# SHEET2.net
KiCad netlist of a schematic drawn in Altium Designer
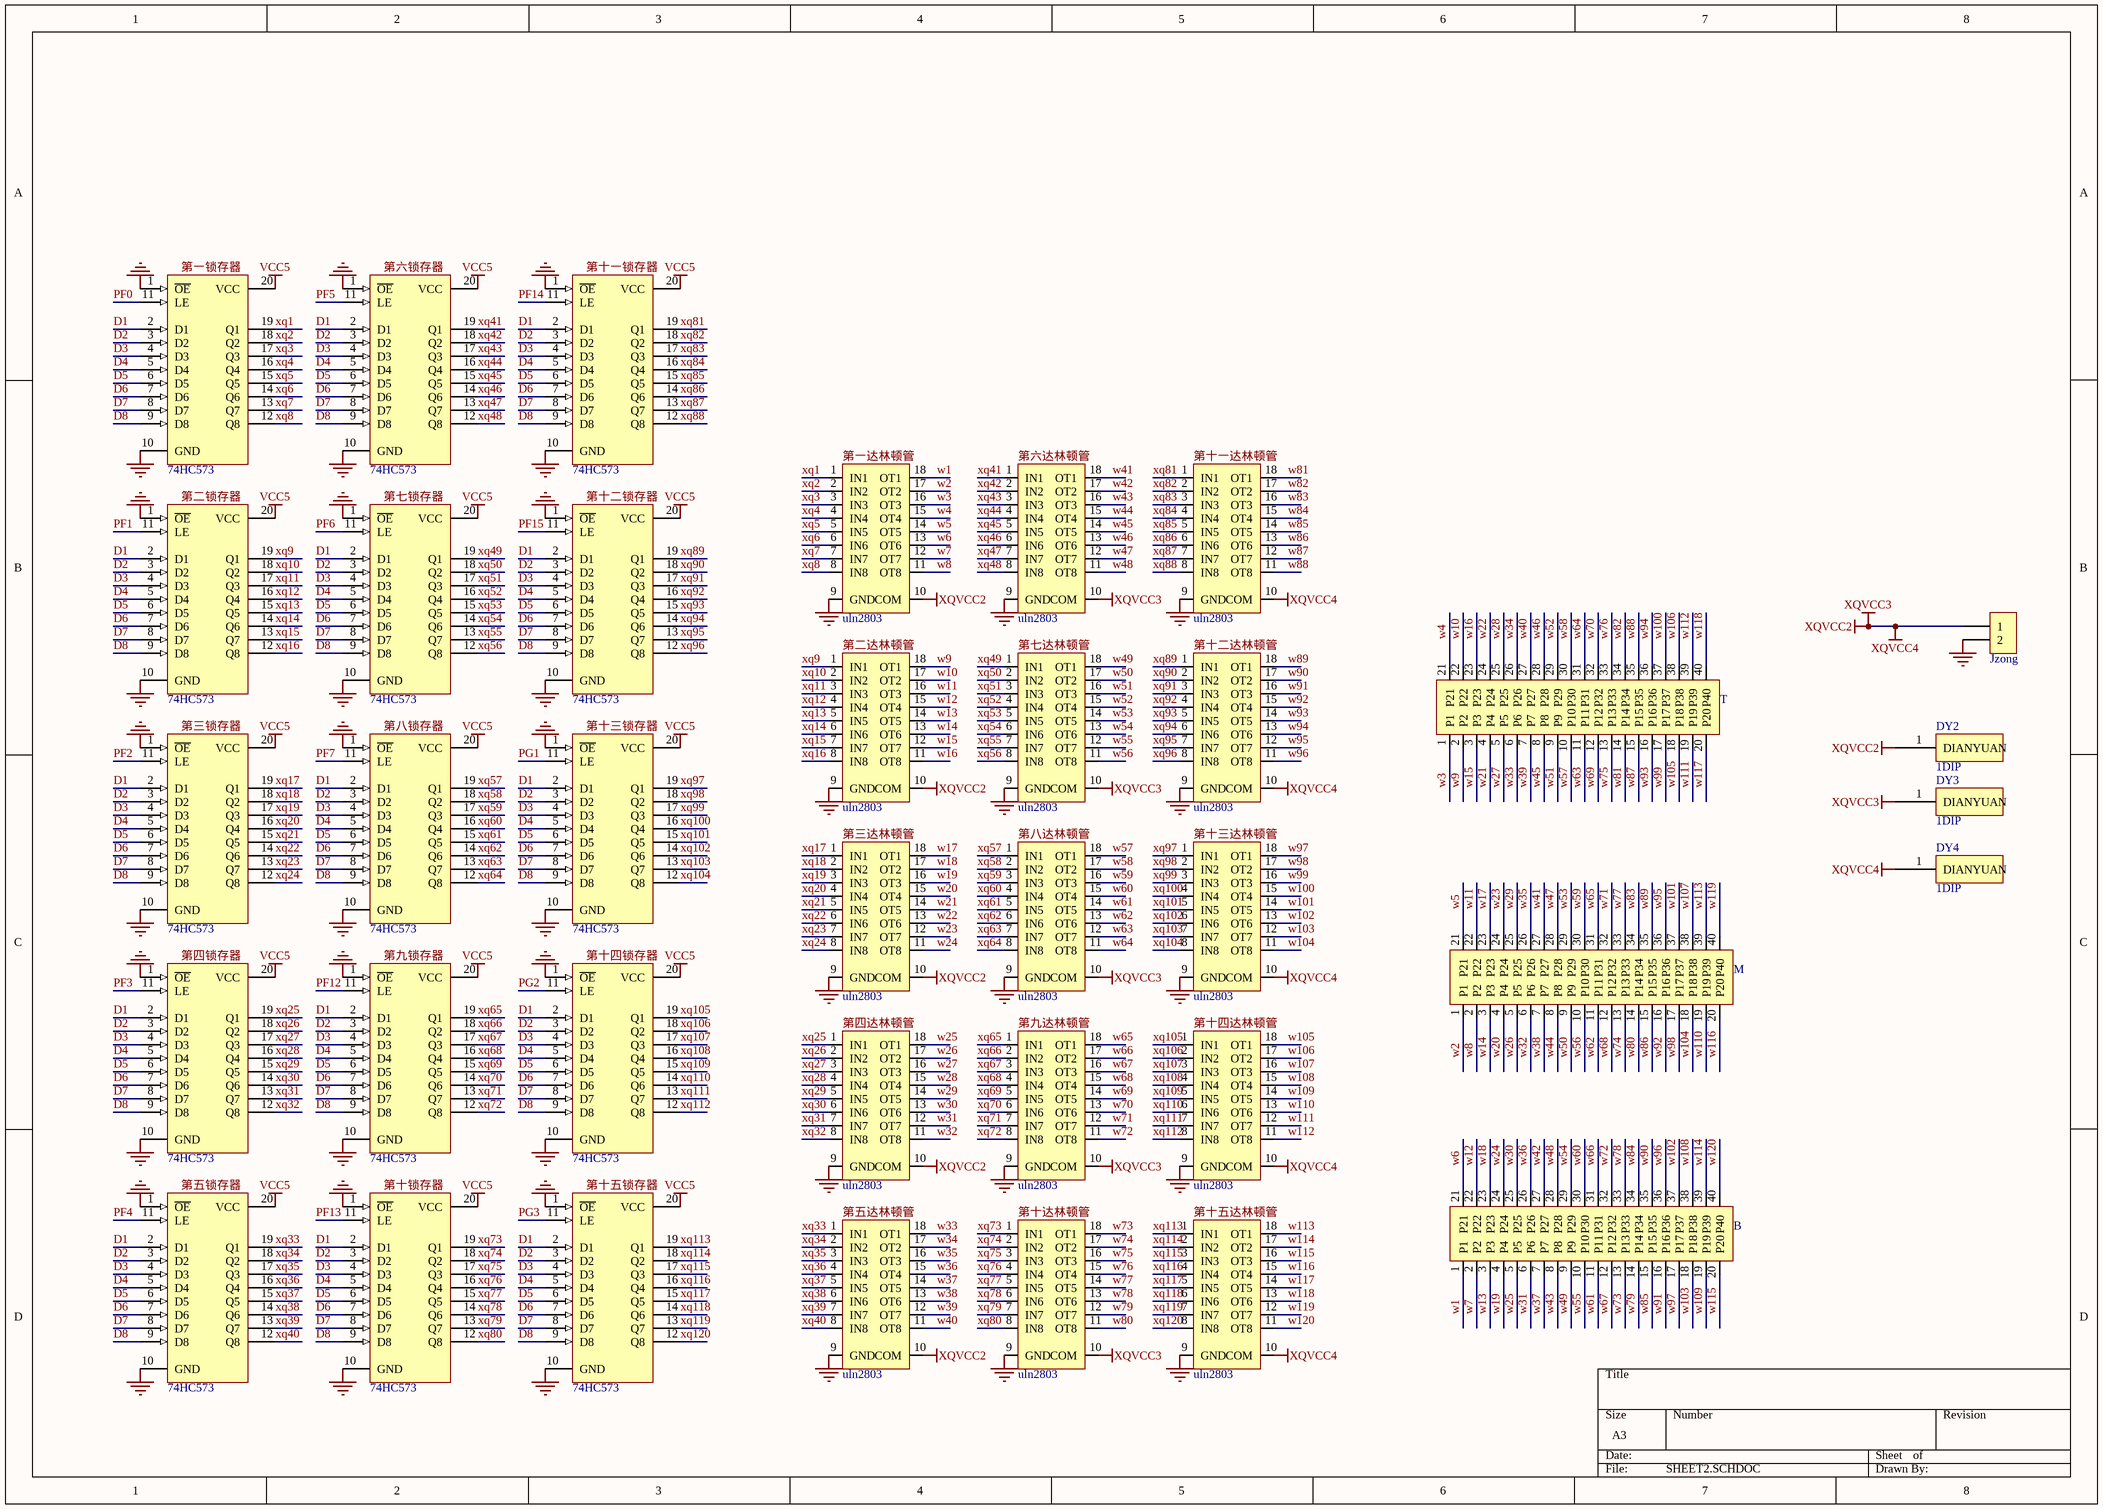
[diagram p0: SHEET2.SCHDOC]

(export (version "E")
  (design (tool "Eeschema 10.0.6"))
  (components
    (comp (ref "573_1")
      (value "74HC573")
      (footprint "SOJ-20")
      (description "Octal D-Type Transparent Latch with 3-State Outputs")
      (fields (field (name "PUBLISHER") "Altium Limited"))
      (libsource (lib "TI Logic Latch") (part "SN74HC573DW"))
    )
    (comp (ref "573_2")
      (value "74HC573")
      (footprint "SOJ-20")
      (description "Octal D-Type Transparent Latch with 3-State Outputs")
      (fields (field (name "PUBLISHER") "Altium Limited"))
      (libsource (lib "TI Logic Latch") (part "SN74HC573DW"))
    )
    (comp (ref "573_3")
      (value "74HC573")
      (footprint "SOJ-20")
      (description "Octal D-Type Transparent Latch with 3-State Outputs")
      (fields (field (name "PUBLISHER") "Altium Limited"))
      (libsource (lib "TI Logic Latch") (part "SN74HC573DW"))
    )
    (comp (ref "573_4")
      (value "74HC573")
      (footprint "SOJ-20")
      (description "Octal D-Type Transparent Latch with 3-State Outputs")
      (fields (field (name "PUBLISHER") "Altium Limited"))
      (libsource (lib "TI Logic Latch") (part "SN74HC573DW"))
    )
    (comp (ref "573_5")
      (value "74HC573")
      (footprint "SOJ-20")
      (description "Octal D-Type Transparent Latch with 3-State Outputs")
      (fields (field (name "PUBLISHER") "Altium Limited"))
      (libsource (lib "TI Logic Latch") (part "SN74HC573DW"))
    )
    (comp (ref "573_6")
      (value "74HC573")
      (footprint "SOJ-20")
      (description "Octal D-Type Transparent Latch with 3-State Outputs")
      (fields (field (name "PUBLISHER") "Altium Limited"))
      (libsource (lib "TI Logic Latch") (part "SN74HC573DW"))
    )
    (comp (ref "573_7")
      (value "74HC573")
      (footprint "SOJ-20")
      (description "Octal D-Type Transparent Latch with 3-State Outputs")
      (fields (field (name "PUBLISHER") "Altium Limited"))
      (libsource (lib "TI Logic Latch") (part "SN74HC573DW"))
    )
    (comp (ref "573_8")
      (value "74HC573")
      (footprint "SOJ-20")
      (description "Octal D-Type Transparent Latch with 3-State Outputs")
      (fields (field (name "PUBLISHER") "Altium Limited"))
      (libsource (lib "TI Logic Latch") (part "SN74HC573DW"))
    )
    (comp (ref "573_9")
      (value "74HC573")
      (footprint "SOJ-20")
      (description "Octal D-Type Transparent Latch with 3-State Outputs")
      (fields (field (name "PUBLISHER") "Altium Limited"))
      (libsource (lib "TI Logic Latch") (part "SN74HC573DW"))
    )
    (comp (ref "573_10")
      (value "74HC573")
      (footprint "SOJ-20")
      (description "Octal D-Type Transparent Latch with 3-State Outputs")
      (fields (field (name "PUBLISHER") "Altium Limited"))
      (libsource (lib "TI Logic Latch") (part "SN74HC573DW"))
    )
    (comp (ref "573_11")
      (value "74HC573")
      (footprint "SOJ-20")
      (description "Octal D-Type Transparent Latch with 3-State Outputs")
      (fields (field (name "PUBLISHER") "Altium Limited"))
      (libsource (lib "TI Logic Latch") (part "SN74HC573DW"))
    )
    (comp (ref "573_12")
      (value "74HC573")
      (footprint "SOJ-20")
      (description "Octal D-Type Transparent Latch with 3-State Outputs")
      (fields (field (name "PUBLISHER") "Altium Limited"))
      (libsource (lib "TI Logic Latch") (part "SN74HC573DW"))
    )
    (comp (ref "573_13")
      (value "74HC573")
      (footprint "SOJ-20")
      (description "Octal D-Type Transparent Latch with 3-State Outputs")
      (fields (field (name "PUBLISHER") "Altium Limited"))
      (libsource (lib "TI Logic Latch") (part "SN74HC573DW"))
    )
    (comp (ref "573_14")
      (value "74HC573")
      (footprint "SOJ-20")
      (description "Octal D-Type Transparent Latch with 3-State Outputs")
      (fields (field (name "PUBLISHER") "Altium Limited"))
      (libsource (lib "TI Logic Latch") (part "SN74HC573DW"))
    )
    (comp (ref "573_15")
      (value "74HC573")
      (footprint "SOJ-20")
      (description "Octal D-Type Transparent Latch with 3-State Outputs")
      (fields (field (name "PUBLISHER") "Altium Limited"))
      (libsource (lib "TI Logic Latch") (part "SN74HC573DW"))
    )
    (comp (ref "B") (value "dubangxian") (footprint "杜邦线插脚") (libsource (lib "一排原理图库") (part "dubangxian")))
    (comp (ref "DY2") (value "1DIP") (footprint "1DIP") (libsource (lib "一排原理图库") (part "1DIP")))
    (comp (ref "DY3") (value "1DIP") (footprint "1DIP") (libsource (lib "一排原理图库") (part "1DIP")))
    (comp (ref "DY4") (value "1DIP") (footprint "1DIP") (libsource (lib "一排原理图库") (part "1DIP")))
    (comp (ref "FD1") (value "uln2803") (footprint "dip-18") (libsource (lib "MW原理图库") (part "uln2803")))
    (comp (ref "FD2") (value "uln2803") (footprint "dip-18") (libsource (lib "MW原理图库") (part "uln2803")))
    (comp (ref "FD3") (value "uln2803") (footprint "dip-18") (libsource (lib "MW原理图库") (part "uln2803")))
    (comp (ref "FD4") (value "uln2803") (footprint "dip-18") (libsource (lib "MW原理图库") (part "uln2803")))
    (comp (ref "FD5") (value "uln2803") (footprint "dip-18") (libsource (lib "MW原理图库") (part "uln2803")))
    (comp (ref "FD6") (value "uln2803") (footprint "dip-18") (libsource (lib "MW原理图库") (part "uln2803")))
    (comp (ref "FD7") (value "uln2803") (footprint "dip-18") (libsource (lib "MW原理图库") (part "uln2803")))
    (comp (ref "FD8") (value "uln2803") (footprint "dip-18") (libsource (lib "MW原理图库") (part "uln2803")))
    (comp (ref "FD9") (value "uln2803") (footprint "dip-18") (libsource (lib "MW原理图库") (part "uln2803")))
    (comp (ref "FD10") (value "uln2803") (footprint "dip-18") (libsource (lib "MW原理图库") (part "uln2803")))
    (comp (ref "FD11") (value "uln2803") (footprint "dip-18") (libsource (lib "MW原理图库") (part "uln2803")))
    (comp (ref "FD12") (value "uln2803") (footprint "dip-18") (libsource (lib "MW原理图库") (part "uln2803")))
    (comp (ref "FD13") (value "uln2803") (footprint "dip-18") (libsource (lib "MW原理图库") (part "uln2803")))
    (comp (ref "FD14") (value "uln2803") (footprint "dip-18") (libsource (lib "MW原理图库") (part "uln2803")))
    (comp (ref "FD15") (value "uln2803") (footprint "dip-18") (libsource (lib "MW原理图库") (part "uln2803")))
    (comp (ref "Jzong")
      (value "CON2")
      (footprint "dc005")
      (description "Connector")
      (libsource (lib "一排") (part "CON2"))
    )
    (comp (ref "M") (value "dubangxian") (footprint "杜邦线插脚") (libsource (lib "一排原理图库") (part "dubangxian")))
    (comp (ref "T") (value "dubangxian") (footprint "杜邦线插脚") (libsource (lib "一排原理图库") (part "dubangxian")))
  )
  (nets
    (net (code "1") (name "/D1") (class "Default")
      (node (ref "573_1") (pin "2") (pinfunction "D1_2") (pintype "input"))
      (node (ref "573_10") (pin "2") (pinfunction "D1_2") (pintype "input"))
      (node (ref "573_11") (pin "2") (pinfunction "D1_2") (pintype "input"))
      (node (ref "573_12") (pin "2") (pinfunction "D1_2") (pintype "input"))
      (node (ref "573_13") (pin "2") (pinfunction "D1_2") (pintype "input"))
      (node (ref "573_14") (pin "2") (pinfunction "D1_2") (pintype "input"))
      (node (ref "573_15") (pin "2") (pinfunction "D1_2") (pintype "input"))
      (node (ref "573_2") (pin "2") (pinfunction "D1_2") (pintype "input"))
      (node (ref "573_3") (pin "2") (pinfunction "D1_2") (pintype "input"))
      (node (ref "573_4") (pin "2") (pinfunction "D1_2") (pintype "input"))
      (node (ref "573_5") (pin "2") (pinfunction "D1_2") (pintype "input"))
      (node (ref "573_6") (pin "2") (pinfunction "D1_2") (pintype "input"))
      (node (ref "573_7") (pin "2") (pinfunction "D1_2") (pintype "input"))
      (node (ref "573_8") (pin "2") (pinfunction "D1_2") (pintype "input"))
      (node (ref "573_9") (pin "2") (pinfunction "D1_2") (pintype "input"))
    )
    (net (code "2") (name "/D2") (class "Default")
      (node (ref "573_1") (pin "3") (pinfunction "D2_3") (pintype "input"))
      (node (ref "573_10") (pin "3") (pinfunction "D2_3") (pintype "input"))
      (node (ref "573_11") (pin "3") (pinfunction "D2_3") (pintype "input"))
      (node (ref "573_12") (pin "3") (pinfunction "D2_3") (pintype "input"))
      (node (ref "573_13") (pin "3") (pinfunction "D2_3") (pintype "input"))
      (node (ref "573_14") (pin "3") (pinfunction "D2_3") (pintype "input"))
      (node (ref "573_15") (pin "3") (pinfunction "D2_3") (pintype "input"))
      (node (ref "573_2") (pin "3") (pinfunction "D2_3") (pintype "input"))
      (node (ref "573_3") (pin "3") (pinfunction "D2_3") (pintype "input"))
      (node (ref "573_4") (pin "3") (pinfunction "D2_3") (pintype "input"))
      (node (ref "573_5") (pin "3") (pinfunction "D2_3") (pintype "input"))
      (node (ref "573_6") (pin "3") (pinfunction "D2_3") (pintype "input"))
      (node (ref "573_7") (pin "3") (pinfunction "D2_3") (pintype "input"))
      (node (ref "573_8") (pin "3") (pinfunction "D2_3") (pintype "input"))
      (node (ref "573_9") (pin "3") (pinfunction "D2_3") (pintype "input"))
    )
    (net (code "3") (name "/D3") (class "Default")
      (node (ref "573_1") (pin "4") (pinfunction "D3_4") (pintype "input"))
      (node (ref "573_10") (pin "4") (pinfunction "D3_4") (pintype "input"))
      (node (ref "573_11") (pin "4") (pinfunction "D3_4") (pintype "input"))
      (node (ref "573_12") (pin "4") (pinfunction "D3_4") (pintype "input"))
      (node (ref "573_13") (pin "4") (pinfunction "D3_4") (pintype "input"))
      (node (ref "573_14") (pin "4") (pinfunction "D3_4") (pintype "input"))
      (node (ref "573_15") (pin "4") (pinfunction "D3_4") (pintype "input"))
      (node (ref "573_2") (pin "4") (pinfunction "D3_4") (pintype "input"))
      (node (ref "573_3") (pin "4") (pinfunction "D3_4") (pintype "input"))
      (node (ref "573_4") (pin "4") (pinfunction "D3_4") (pintype "input"))
      (node (ref "573_5") (pin "4") (pinfunction "D3_4") (pintype "input"))
      (node (ref "573_6") (pin "4") (pinfunction "D3_4") (pintype "input"))
      (node (ref "573_7") (pin "4") (pinfunction "D3_4") (pintype "input"))
      (node (ref "573_8") (pin "4") (pinfunction "D3_4") (pintype "input"))
      (node (ref "573_9") (pin "4") (pinfunction "D3_4") (pintype "input"))
    )
    (net (code "4") (name "/D4") (class "Default")
      (node (ref "573_1") (pin "5") (pinfunction "D4_5") (pintype "input"))
      (node (ref "573_10") (pin "5") (pinfunction "D4_5") (pintype "input"))
      (node (ref "573_11") (pin "5") (pinfunction "D4_5") (pintype "input"))
      (node (ref "573_12") (pin "5") (pinfunction "D4_5") (pintype "input"))
      (node (ref "573_13") (pin "5") (pinfunction "D4_5") (pintype "input"))
      (node (ref "573_14") (pin "5") (pinfunction "D4_5") (pintype "input"))
      (node (ref "573_15") (pin "5") (pinfunction "D4_5") (pintype "input"))
      (node (ref "573_2") (pin "5") (pinfunction "D4_5") (pintype "input"))
      (node (ref "573_3") (pin "5") (pinfunction "D4_5") (pintype "input"))
      (node (ref "573_4") (pin "5") (pinfunction "D4_5") (pintype "input"))
      (node (ref "573_5") (pin "5") (pinfunction "D4_5") (pintype "input"))
      (node (ref "573_6") (pin "5") (pinfunction "D4_5") (pintype "input"))
      (node (ref "573_7") (pin "5") (pinfunction "D4_5") (pintype "input"))
      (node (ref "573_8") (pin "5") (pinfunction "D4_5") (pintype "input"))
      (node (ref "573_9") (pin "5") (pinfunction "D4_5") (pintype "input"))
    )
    (net (code "5") (name "/D5") (class "Default")
      (node (ref "573_1") (pin "6") (pinfunction "D5_6") (pintype "input"))
      (node (ref "573_10") (pin "6") (pinfunction "D5_6") (pintype "input"))
      (node (ref "573_11") (pin "6") (pinfunction "D5_6") (pintype "input"))
      (node (ref "573_12") (pin "6") (pinfunction "D5_6") (pintype "input"))
      (node (ref "573_13") (pin "6") (pinfunction "D5_6") (pintype "input"))
      (node (ref "573_14") (pin "6") (pinfunction "D5_6") (pintype "input"))
      (node (ref "573_15") (pin "6") (pinfunction "D5_6") (pintype "input"))
      (node (ref "573_2") (pin "6") (pinfunction "D5_6") (pintype "input"))
      (node (ref "573_3") (pin "6") (pinfunction "D5_6") (pintype "input"))
      (node (ref "573_4") (pin "6") (pinfunction "D5_6") (pintype "input"))
      (node (ref "573_5") (pin "6") (pinfunction "D5_6") (pintype "input"))
      (node (ref "573_6") (pin "6") (pinfunction "D5_6") (pintype "input"))
      (node (ref "573_7") (pin "6") (pinfunction "D5_6") (pintype "input"))
      (node (ref "573_8") (pin "6") (pinfunction "D5_6") (pintype "input"))
      (node (ref "573_9") (pin "6") (pinfunction "D5_6") (pintype "input"))
    )
    (net (code "6") (name "/D6") (class "Default")
      (node (ref "573_1") (pin "7") (pinfunction "D6_7") (pintype "input"))
      (node (ref "573_10") (pin "7") (pinfunction "D6_7") (pintype "input"))
      (node (ref "573_11") (pin "7") (pinfunction "D6_7") (pintype "input"))
      (node (ref "573_12") (pin "7") (pinfunction "D6_7") (pintype "input"))
      (node (ref "573_13") (pin "7") (pinfunction "D6_7") (pintype "input"))
      (node (ref "573_14") (pin "7") (pinfunction "D6_7") (pintype "input"))
      (node (ref "573_15") (pin "7") (pinfunction "D6_7") (pintype "input"))
      (node (ref "573_2") (pin "7") (pinfunction "D6_7") (pintype "input"))
      (node (ref "573_3") (pin "7") (pinfunction "D6_7") (pintype "input"))
      (node (ref "573_4") (pin "7") (pinfunction "D6_7") (pintype "input"))
      (node (ref "573_5") (pin "7") (pinfunction "D6_7") (pintype "input"))
      (node (ref "573_6") (pin "7") (pinfunction "D6_7") (pintype "input"))
      (node (ref "573_7") (pin "7") (pinfunction "D6_7") (pintype "input"))
      (node (ref "573_8") (pin "7") (pinfunction "D6_7") (pintype "input"))
      (node (ref "573_9") (pin "7") (pinfunction "D6_7") (pintype "input"))
    )
    (net (code "7") (name "/D7") (class "Default")
      (node (ref "573_1") (pin "8") (pinfunction "D7_8") (pintype "input"))
      (node (ref "573_10") (pin "8") (pinfunction "D7_8") (pintype "input"))
      (node (ref "573_11") (pin "8") (pinfunction "D7_8") (pintype "input"))
      (node (ref "573_12") (pin "8") (pinfunction "D7_8") (pintype "input"))
      (node (ref "573_13") (pin "8") (pinfunction "D7_8") (pintype "input"))
      (node (ref "573_14") (pin "8") (pinfunction "D7_8") (pintype "input"))
      (node (ref "573_15") (pin "8") (pinfunction "D7_8") (pintype "input"))
      (node (ref "573_2") (pin "8") (pinfunction "D7_8") (pintype "input"))
      (node (ref "573_3") (pin "8") (pinfunction "D7_8") (pintype "input"))
      (node (ref "573_4") (pin "8") (pinfunction "D7_8") (pintype "input"))
      (node (ref "573_5") (pin "8") (pinfunction "D7_8") (pintype "input"))
      (node (ref "573_6") (pin "8") (pinfunction "D7_8") (pintype "input"))
      (node (ref "573_7") (pin "8") (pinfunction "D7_8") (pintype "input"))
      (node (ref "573_8") (pin "8") (pinfunction "D7_8") (pintype "input"))
      (node (ref "573_9") (pin "8") (pinfunction "D7_8") (pintype "input"))
    )
    (net (code "8") (name "/D8") (class "Default")
      (node (ref "573_1") (pin "9") (pinfunction "D8_9") (pintype "input"))
      (node (ref "573_10") (pin "9") (pinfunction "D8_9") (pintype "input"))
      (node (ref "573_11") (pin "9") (pinfunction "D8_9") (pintype "input"))
      (node (ref "573_12") (pin "9") (pinfunction "D8_9") (pintype "input"))
      (node (ref "573_13") (pin "9") (pinfunction "D8_9") (pintype "input"))
      (node (ref "573_14") (pin "9") (pinfunction "D8_9") (pintype "input"))
      (node (ref "573_15") (pin "9") (pinfunction "D8_9") (pintype "input"))
      (node (ref "573_2") (pin "9") (pinfunction "D8_9") (pintype "input"))
      (node (ref "573_3") (pin "9") (pinfunction "D8_9") (pintype "input"))
      (node (ref "573_4") (pin "9") (pinfunction "D8_9") (pintype "input"))
      (node (ref "573_5") (pin "9") (pinfunction "D8_9") (pintype "input"))
      (node (ref "573_6") (pin "9") (pinfunction "D8_9") (pintype "input"))
      (node (ref "573_7") (pin "9") (pinfunction "D8_9") (pintype "input"))
      (node (ref "573_8") (pin "9") (pinfunction "D8_9") (pintype "input"))
      (node (ref "573_9") (pin "9") (pinfunction "D8_9") (pintype "input"))
    )
    (net (code "9") (name "/PF0") (class "Default")
      (node (ref "573_1") (pin "11") (pinfunction "LE_11") (pintype "input"))
    )
    (net (code "10") (name "/PF1") (class "Default")
      (node (ref "573_2") (pin "11") (pinfunction "LE_11") (pintype "input"))
    )
    (net (code "11") (name "/PF2") (class "Default")
      (node (ref "573_3") (pin "11") (pinfunction "LE_11") (pintype "input"))
    )
    (net (code "12") (name "/PF3") (class "Default")
      (node (ref "573_4") (pin "11") (pinfunction "LE_11") (pintype "input"))
    )
    (net (code "13") (name "/PF4") (class "Default")
      (node (ref "573_5") (pin "11") (pinfunction "LE_11") (pintype "input"))
    )
    (net (code "14") (name "/PF5") (class "Default")
      (node (ref "573_7") (pin "11") (pinfunction "LE_11") (pintype "input"))
    )
    (net (code "15") (name "/PF6") (class "Default")
      (node (ref "573_8") (pin "11") (pinfunction "LE_11") (pintype "input"))
    )
    (net (code "16") (name "/PF7") (class "Default")
      (node (ref "573_9") (pin "11") (pinfunction "LE_11") (pintype "input"))
    )
    (net (code "17") (name "/PF12") (class "Default")
      (node (ref "573_10") (pin "11") (pinfunction "LE_11") (pintype "input"))
    )
    (net (code "18") (name "/PF13") (class "Default")
      (node (ref "573_11") (pin "11") (pinfunction "LE_11") (pintype "input"))
    )
    (net (code "19") (name "/PF14") (class "Default")
      (node (ref "573_12") (pin "11") (pinfunction "LE_11") (pintype "input"))
    )
    (net (code "20") (name "/PF15") (class "Default")
      (node (ref "573_13") (pin "11") (pinfunction "LE_11") (pintype "input"))
    )
    (net (code "21") (name "/PG1") (class "Default")
      (node (ref "573_14") (pin "11") (pinfunction "LE_11") (pintype "input"))
    )
    (net (code "22") (name "/PG2") (class "Default")
      (node (ref "573_15") (pin "11") (pinfunction "LE_11") (pintype "input"))
    )
    (net (code "23") (name "/PG3") (class "Default")
      (node (ref "573_6") (pin "11") (pinfunction "LE_11") (pintype "input"))
    )
    (net (code "24") (name "/w1") (class "Default")
      (node (ref "B") (pin "1") (pinfunction "P1_1") (pintype "passive"))
      (node (ref "FD1") (pin "18") (pinfunction "OT1_18") (pintype "passive"))
    )
    (net (code "25") (name "/w2") (class "Default")
      (node (ref "FD1") (pin "17") (pinfunction "OT2_17") (pintype "passive"))
      (node (ref "M") (pin "1") (pinfunction "P1_1") (pintype "passive"))
    )
    (net (code "26") (name "/w3") (class "Default")
      (node (ref "FD1") (pin "16") (pinfunction "OT3_16") (pintype "passive"))
      (node (ref "T") (pin "1") (pinfunction "P1_1") (pintype "passive"))
    )
    (net (code "27") (name "/w4") (class "Default")
      (node (ref "FD1") (pin "15") (pinfunction "OT4_15") (pintype "passive"))
      (node (ref "T") (pin "21") (pinfunction "P21_21") (pintype "passive"))
    )
    (net (code "28") (name "/w5") (class "Default")
      (node (ref "FD1") (pin "14") (pinfunction "OT5_14") (pintype "passive"))
      (node (ref "M") (pin "21") (pinfunction "P21_21") (pintype "passive"))
    )
    (net (code "29") (name "/w6") (class "Default")
      (node (ref "B") (pin "21") (pinfunction "P21_21") (pintype "passive"))
      (node (ref "FD1") (pin "13") (pinfunction "OT6_13") (pintype "passive"))
    )
    (net (code "30") (name "/w7") (class "Default")
      (node (ref "B") (pin "2") (pinfunction "P2_2") (pintype "passive"))
      (node (ref "FD1") (pin "12") (pinfunction "OT7_12") (pintype "passive"))
    )
    (net (code "31") (name "/w8") (class "Default")
      (node (ref "FD1") (pin "11") (pinfunction "OT8_11") (pintype "passive"))
      (node (ref "M") (pin "2") (pinfunction "P2_2") (pintype "passive"))
    )
    (net (code "32") (name "/w9") (class "Default")
      (node (ref "FD2") (pin "18") (pinfunction "OT1_18") (pintype "passive"))
      (node (ref "T") (pin "2") (pinfunction "P2_2") (pintype "passive"))
    )
    (net (code "33") (name "/w10") (class "Default")
      (node (ref "FD2") (pin "17") (pinfunction "OT2_17") (pintype "passive"))
      (node (ref "T") (pin "22") (pinfunction "P22_22") (pintype "passive"))
    )
    (net (code "34") (name "/w11") (class "Default")
      (node (ref "FD2") (pin "16") (pinfunction "OT3_16") (pintype "passive"))
      (node (ref "M") (pin "22") (pinfunction "P22_22") (pintype "passive"))
    )
    (net (code "35") (name "/w12") (class "Default")
      (node (ref "B") (pin "22") (pinfunction "P22_22") (pintype "passive"))
      (node (ref "FD2") (pin "15") (pinfunction "OT4_15") (pintype "passive"))
    )
    (net (code "36") (name "/w13") (class "Default")
      (node (ref "B") (pin "3") (pinfunction "P3_3") (pintype "passive"))
      (node (ref "FD2") (pin "14") (pinfunction "OT5_14") (pintype "passive"))
    )
    (net (code "37") (name "/w14") (class "Default")
      (node (ref "FD2") (pin "13") (pinfunction "OT6_13") (pintype "passive"))
      (node (ref "M") (pin "3") (pinfunction "P3_3") (pintype "passive"))
    )
    (net (code "38") (name "/w15") (class "Default")
      (node (ref "FD2") (pin "12") (pinfunction "OT7_12") (pintype "passive"))
      (node (ref "T") (pin "3") (pinfunction "P3_3") (pintype "passive"))
    )
    (net (code "39") (name "/w16") (class "Default")
      (node (ref "FD2") (pin "11") (pinfunction "OT8_11") (pintype "passive"))
      (node (ref "T") (pin "23") (pinfunction "P23_23") (pintype "passive"))
    )
    (net (code "40") (name "/w17") (class "Default")
      (node (ref "FD3") (pin "18") (pinfunction "OT1_18") (pintype "passive"))
      (node (ref "M") (pin "23") (pinfunction "P23_23") (pintype "passive"))
    )
    (net (code "41") (name "/w18") (class "Default")
      (node (ref "B") (pin "23") (pinfunction "P23_23") (pintype "passive"))
      (node (ref "FD3") (pin "17") (pinfunction "OT2_17") (pintype "passive"))
    )
    (net (code "42") (name "/w19") (class "Default")
      (node (ref "B") (pin "4") (pinfunction "P4_4") (pintype "passive"))
      (node (ref "FD3") (pin "16") (pinfunction "OT3_16") (pintype "passive"))
    )
    (net (code "43") (name "/w20") (class "Default")
      (node (ref "FD3") (pin "15") (pinfunction "OT4_15") (pintype "passive"))
      (node (ref "M") (pin "4") (pinfunction "P4_4") (pintype "passive"))
    )
    (net (code "44") (name "/w21") (class "Default")
      (node (ref "FD3") (pin "14") (pinfunction "OT5_14") (pintype "passive"))
      (node (ref "T") (pin "4") (pinfunction "P4_4") (pintype "passive"))
    )
    (net (code "45") (name "/w22") (class "Default")
      (node (ref "FD3") (pin "13") (pinfunction "OT6_13") (pintype "passive"))
      (node (ref "T") (pin "24") (pinfunction "P24_24") (pintype "passive"))
    )
    (net (code "46") (name "/w23") (class "Default")
      (node (ref "FD3") (pin "12") (pinfunction "OT7_12") (pintype "passive"))
      (node (ref "M") (pin "24") (pinfunction "P24_24") (pintype "passive"))
    )
    (net (code "47") (name "/w24") (class "Default")
      (node (ref "B") (pin "24") (pinfunction "P24_24") (pintype "passive"))
      (node (ref "FD3") (pin "11") (pinfunction "OT8_11") (pintype "passive"))
    )
    (net (code "48") (name "/w25") (class "Default")
      (node (ref "B") (pin "5") (pinfunction "P5_5") (pintype "passive"))
      (node (ref "FD4") (pin "18") (pinfunction "OT1_18") (pintype "passive"))
    )
    (net (code "49") (name "/w26") (class "Default")
      (node (ref "FD4") (pin "17") (pinfunction "OT2_17") (pintype "passive"))
      (node (ref "M") (pin "5") (pinfunction "P5_5") (pintype "passive"))
    )
    (net (code "50") (name "/w27") (class "Default")
      (node (ref "FD4") (pin "16") (pinfunction "OT3_16") (pintype "passive"))
      (node (ref "T") (pin "5") (pinfunction "P5_5") (pintype "passive"))
    )
    (net (code "51") (name "/w28") (class "Default")
      (node (ref "FD4") (pin "15") (pinfunction "OT4_15") (pintype "passive"))
      (node (ref "T") (pin "25") (pinfunction "P25_25") (pintype "passive"))
    )
    (net (code "52") (name "/w29") (class "Default")
      (node (ref "FD4") (pin "14") (pinfunction "OT5_14") (pintype "passive"))
      (node (ref "M") (pin "25") (pinfunction "P25_25") (pintype "passive"))
    )
    (net (code "53") (name "/w30") (class "Default")
      (node (ref "B") (pin "25") (pinfunction "P25_25") (pintype "passive"))
      (node (ref "FD4") (pin "13") (pinfunction "OT6_13") (pintype "passive"))
    )
    (net (code "54") (name "/w31") (class "Default")
      (node (ref "B") (pin "6") (pinfunction "P6_6") (pintype "passive"))
      (node (ref "FD4") (pin "12") (pinfunction "OT7_12") (pintype "passive"))
    )
    (net (code "55") (name "/w32") (class "Default")
      (node (ref "FD4") (pin "11") (pinfunction "OT8_11") (pintype "passive"))
      (node (ref "M") (pin "6") (pinfunction "P6_6") (pintype "passive"))
    )
    (net (code "56") (name "/w33") (class "Default")
      (node (ref "FD5") (pin "18") (pinfunction "OT1_18") (pintype "passive"))
      (node (ref "T") (pin "6") (pinfunction "P6_6") (pintype "passive"))
    )
    (net (code "57") (name "/w34") (class "Default")
      (node (ref "FD5") (pin "17") (pinfunction "OT2_17") (pintype "passive"))
      (node (ref "T") (pin "26") (pinfunction "P26_26") (pintype "passive"))
    )
    (net (code "58") (name "/w35") (class "Default")
      (node (ref "FD5") (pin "16") (pinfunction "OT3_16") (pintype "passive"))
      (node (ref "M") (pin "26") (pinfunction "P26_26") (pintype "passive"))
    )
    (net (code "59") (name "/w36") (class "Default")
      (node (ref "B") (pin "26") (pinfunction "P26_26") (pintype "passive"))
      (node (ref "FD5") (pin "15") (pinfunction "OT4_15") (pintype "passive"))
    )
    (net (code "60") (name "/w37") (class "Default")
      (node (ref "B") (pin "7") (pinfunction "P7_7") (pintype "passive"))
      (node (ref "FD5") (pin "14") (pinfunction "OT5_14") (pintype "passive"))
    )
    (net (code "61") (name "/w38") (class "Default")
      (node (ref "FD5") (pin "13") (pinfunction "OT6_13") (pintype "passive"))
      (node (ref "M") (pin "7") (pinfunction "P7_7") (pintype "passive"))
    )
    (net (code "62") (name "/w39") (class "Default")
      (node (ref "FD5") (pin "12") (pinfunction "OT7_12") (pintype "passive"))
      (node (ref "T") (pin "7") (pinfunction "P7_7") (pintype "passive"))
    )
    (net (code "63") (name "/w40") (class "Default")
      (node (ref "FD5") (pin "11") (pinfunction "OT8_11") (pintype "passive"))
      (node (ref "T") (pin "27") (pinfunction "P27_27") (pintype "passive"))
    )
    (net (code "64") (name "/w41") (class "Default")
      (node (ref "FD6") (pin "18") (pinfunction "OT1_18") (pintype "passive"))
      (node (ref "M") (pin "27") (pinfunction "P27_27") (pintype "passive"))
    )
    (net (code "65") (name "/w42") (class "Default")
      (node (ref "B") (pin "27") (pinfunction "P27_27") (pintype "passive"))
      (node (ref "FD6") (pin "17") (pinfunction "OT2_17") (pintype "passive"))
    )
    (net (code "66") (name "/w43") (class "Default")
      (node (ref "B") (pin "8") (pinfunction "P8_8") (pintype "passive"))
      (node (ref "FD6") (pin "16") (pinfunction "OT3_16") (pintype "passive"))
    )
    (net (code "67") (name "/w44") (class "Default")
      (node (ref "FD6") (pin "15") (pinfunction "OT4_15") (pintype "passive"))
      (node (ref "M") (pin "8") (pinfunction "P8_8") (pintype "passive"))
    )
    (net (code "68") (name "/w45") (class "Default")
      (node (ref "FD6") (pin "14") (pinfunction "OT5_14") (pintype "passive"))
      (node (ref "T") (pin "8") (pinfunction "P8_8") (pintype "passive"))
    )
    (net (code "69") (name "/w46") (class "Default")
      (node (ref "FD6") (pin "13") (pinfunction "OT6_13") (pintype "passive"))
      (node (ref "T") (pin "28") (pinfunction "P28_28") (pintype "passive"))
    )
    (net (code "70") (name "/w47") (class "Default")
      (node (ref "FD6") (pin "12") (pinfunction "OT7_12") (pintype "passive"))
      (node (ref "M") (pin "28") (pinfunction "P28_28") (pintype "passive"))
    )
    (net (code "71") (name "/w48") (class "Default")
      (node (ref "B") (pin "28") (pinfunction "P28_28") (pintype "passive"))
      (node (ref "FD6") (pin "11") (pinfunction "OT8_11") (pintype "passive"))
    )
    (net (code "72") (name "/w49") (class "Default")
      (node (ref "B") (pin "9") (pinfunction "P9_9") (pintype "passive"))
      (node (ref "FD7") (pin "18") (pinfunction "OT1_18") (pintype "passive"))
    )
    (net (code "73") (name "/w50") (class "Default")
      (node (ref "FD7") (pin "17") (pinfunction "OT2_17") (pintype "passive"))
      (node (ref "M") (pin "9") (pinfunction "P9_9") (pintype "passive"))
    )
    (net (code "74") (name "/w51") (class "Default")
      (node (ref "FD7") (pin "16") (pinfunction "OT3_16") (pintype "passive"))
      (node (ref "T") (pin "9") (pinfunction "P9_9") (pintype "passive"))
    )
    (net (code "75") (name "/w52") (class "Default")
      (node (ref "FD7") (pin "15") (pinfunction "OT4_15") (pintype "passive"))
      (node (ref "T") (pin "29") (pinfunction "P29_29") (pintype "passive"))
    )
    (net (code "76") (name "/w53") (class "Default")
      (node (ref "FD7") (pin "14") (pinfunction "OT5_14") (pintype "passive"))
      (node (ref "M") (pin "29") (pinfunction "P29_29") (pintype "passive"))
    )
    (net (code "77") (name "/w54") (class "Default")
      (node (ref "B") (pin "29") (pinfunction "P29_29") (pintype "passive"))
      (node (ref "FD7") (pin "13") (pinfunction "OT6_13") (pintype "passive"))
    )
    (net (code "78") (name "/w55") (class "Default")
      (node (ref "B") (pin "10") (pinfunction "P10_10") (pintype "passive"))
      (node (ref "FD7") (pin "12") (pinfunction "OT7_12") (pintype "passive"))
    )
    (net (code "79") (name "/w56") (class "Default")
      (node (ref "FD7") (pin "11") (pinfunction "OT8_11") (pintype "passive"))
      (node (ref "M") (pin "10") (pinfunction "P10_10") (pintype "passive"))
    )
    (net (code "80") (name "/w57") (class "Default")
      (node (ref "FD8") (pin "18") (pinfunction "OT1_18") (pintype "passive"))
      (node (ref "T") (pin "10") (pinfunction "P10_10") (pintype "passive"))
    )
    (net (code "81") (name "/w58") (class "Default")
      (node (ref "FD8") (pin "17") (pinfunction "OT2_17") (pintype "passive"))
      (node (ref "T") (pin "30") (pinfunction "P30_30") (pintype "passive"))
    )
    (net (code "82") (name "/w59") (class "Default")
      (node (ref "FD8") (pin "16") (pinfunction "OT3_16") (pintype "passive"))
      (node (ref "M") (pin "30") (pinfunction "P30_30") (pintype "passive"))
    )
    (net (code "83") (name "/w60") (class "Default")
      (node (ref "B") (pin "30") (pinfunction "P30_30") (pintype "passive"))
      (node (ref "FD8") (pin "15") (pinfunction "OT4_15") (pintype "passive"))
    )
    (net (code "84") (name "/w61") (class "Default")
      (node (ref "B") (pin "11") (pinfunction "P11_11") (pintype "passive"))
      (node (ref "FD8") (pin "14") (pinfunction "OT5_14") (pintype "passive"))
    )
    (net (code "85") (name "/w62") (class "Default")
      (node (ref "FD8") (pin "13") (pinfunction "OT6_13") (pintype "passive"))
      (node (ref "M") (pin "11") (pinfunction "P11_11") (pintype "passive"))
    )
    (net (code "86") (name "/w63") (class "Default")
      (node (ref "FD8") (pin "12") (pinfunction "OT7_12") (pintype "passive"))
      (node (ref "T") (pin "11") (pinfunction "P11_11") (pintype "passive"))
    )
    (net (code "87") (name "/w64") (class "Default")
      (node (ref "FD8") (pin "11") (pinfunction "OT8_11") (pintype "passive"))
      (node (ref "T") (pin "31") (pinfunction "P31_31") (pintype "passive"))
    )
    (net (code "88") (name "/w65") (class "Default")
      (node (ref "FD9") (pin "18") (pinfunction "OT1_18") (pintype "passive"))
      (node (ref "M") (pin "31") (pinfunction "P31_31") (pintype "passive"))
    )
    (net (code "89") (name "/w66") (class "Default")
      (node (ref "B") (pin "31") (pinfunction "P31_31") (pintype "passive"))
      (node (ref "FD9") (pin "17") (pinfunction "OT2_17") (pintype "passive"))
    )
    (net (code "90") (name "/w67") (class "Default")
      (node (ref "B") (pin "12") (pinfunction "P12_12") (pintype "passive"))
      (node (ref "FD9") (pin "16") (pinfunction "OT3_16") (pintype "passive"))
    )
    (net (code "91") (name "/w68") (class "Default")
      (node (ref "FD9") (pin "15") (pinfunction "OT4_15") (pintype "passive"))
      (node (ref "M") (pin "12") (pinfunction "P12_12") (pintype "passive"))
    )
    (net (code "92") (name "/w69") (class "Default")
      (node (ref "FD9") (pin "14") (pinfunction "OT5_14") (pintype "passive"))
      (node (ref "T") (pin "12") (pinfunction "P12_12") (pintype "passive"))
    )
    (net (code "93") (name "/w70") (class "Default")
      (node (ref "FD9") (pin "13") (pinfunction "OT6_13") (pintype "passive"))
      (node (ref "T") (pin "32") (pinfunction "P32_32") (pintype "passive"))
    )
    (net (code "94") (name "/w71") (class "Default")
      (node (ref "FD9") (pin "12") (pinfunction "OT7_12") (pintype "passive"))
      (node (ref "M") (pin "32") (pinfunction "P32_32") (pintype "passive"))
    )
    (net (code "95") (name "/w72") (class "Default")
      (node (ref "B") (pin "32") (pinfunction "P32_32") (pintype "passive"))
      (node (ref "FD9") (pin "11") (pinfunction "OT8_11") (pintype "passive"))
    )
    (net (code "96") (name "/w73") (class "Default")
      (node (ref "B") (pin "13") (pinfunction "P13_13") (pintype "passive"))
      (node (ref "FD10") (pin "18") (pinfunction "OT1_18") (pintype "passive"))
    )
    (net (code "97") (name "/w74") (class "Default")
      (node (ref "FD10") (pin "17") (pinfunction "OT2_17") (pintype "passive"))
      (node (ref "M") (pin "13") (pinfunction "P13_13") (pintype "passive"))
    )
    (net (code "98") (name "/w75") (class "Default")
      (node (ref "FD10") (pin "16") (pinfunction "OT3_16") (pintype "passive"))
      (node (ref "T") (pin "13") (pinfunction "P13_13") (pintype "passive"))
    )
    (net (code "99") (name "/w76") (class "Default")
      (node (ref "FD10") (pin "15") (pinfunction "OT4_15") (pintype "passive"))
      (node (ref "T") (pin "33") (pinfunction "P33_33") (pintype "passive"))
    )
    (net (code "100") (name "/w77") (class "Default")
      (node (ref "FD10") (pin "14") (pinfunction "OT5_14") (pintype "passive"))
      (node (ref "M") (pin "33") (pinfunction "P33_33") (pintype "passive"))
    )
    (net (code "101") (name "/w78") (class "Default")
      (node (ref "B") (pin "33") (pinfunction "P33_33") (pintype "passive"))
      (node (ref "FD10") (pin "13") (pinfunction "OT6_13") (pintype "passive"))
    )
    (net (code "102") (name "/w79") (class "Default")
      (node (ref "B") (pin "14") (pinfunction "P14_14") (pintype "passive"))
      (node (ref "FD10") (pin "12") (pinfunction "OT7_12") (pintype "passive"))
    )
    (net (code "103") (name "/w80") (class "Default")
      (node (ref "FD10") (pin "11") (pinfunction "OT8_11") (pintype "passive"))
      (node (ref "M") (pin "14") (pinfunction "P14_14") (pintype "passive"))
    )
    (net (code "104") (name "/w81") (class "Default")
      (node (ref "FD11") (pin "18") (pinfunction "OT1_18") (pintype "passive"))
      (node (ref "T") (pin "14") (pinfunction "P14_14") (pintype "passive"))
    )
    (net (code "105") (name "/w82") (class "Default")
      (node (ref "FD11") (pin "17") (pinfunction "OT2_17") (pintype "passive"))
      (node (ref "T") (pin "34") (pinfunction "P34_34") (pintype "passive"))
    )
    (net (code "106") (name "/w83") (class "Default")
      (node (ref "FD11") (pin "16") (pinfunction "OT3_16") (pintype "passive"))
      (node (ref "M") (pin "34") (pinfunction "P34_34") (pintype "passive"))
    )
    (net (code "107") (name "/w84") (class "Default")
      (node (ref "B") (pin "34") (pinfunction "P34_34") (pintype "passive"))
      (node (ref "FD11") (pin "15") (pinfunction "OT4_15") (pintype "passive"))
    )
    (net (code "108") (name "/w85") (class "Default")
      (node (ref "B") (pin "15") (pinfunction "P15_15") (pintype "passive"))
      (node (ref "FD11") (pin "14") (pinfunction "OT5_14") (pintype "passive"))
    )
    (net (code "109") (name "/w86") (class "Default")
      (node (ref "FD11") (pin "13") (pinfunction "OT6_13") (pintype "passive"))
      (node (ref "M") (pin "15") (pinfunction "P15_15") (pintype "passive"))
    )
    (net (code "110") (name "/w87") (class "Default")
      (node (ref "FD11") (pin "12") (pinfunction "OT7_12") (pintype "passive"))
      (node (ref "T") (pin "15") (pinfunction "P15_15") (pintype "passive"))
    )
    (net (code "111") (name "/w88") (class "Default")
      (node (ref "FD11") (pin "11") (pinfunction "OT8_11") (pintype "passive"))
      (node (ref "T") (pin "35") (pinfunction "P35_35") (pintype "passive"))
    )
    (net (code "112") (name "/w89") (class "Default")
      (node (ref "FD12") (pin "18") (pinfunction "OT1_18") (pintype "passive"))
      (node (ref "M") (pin "35") (pinfunction "P35_35") (pintype "passive"))
    )
    (net (code "113") (name "/w90") (class "Default")
      (node (ref "B") (pin "35") (pinfunction "P35_35") (pintype "passive"))
      (node (ref "FD12") (pin "17") (pinfunction "OT2_17") (pintype "passive"))
    )
    (net (code "114") (name "/w91") (class "Default")
      (node (ref "B") (pin "16") (pinfunction "P16_16") (pintype "passive"))
      (node (ref "FD12") (pin "16") (pinfunction "OT3_16") (pintype "passive"))
    )
    (net (code "115") (name "/w92") (class "Default")
      (node (ref "FD12") (pin "15") (pinfunction "OT4_15") (pintype "passive"))
      (node (ref "M") (pin "16") (pinfunction "P16_16") (pintype "passive"))
    )
    (net (code "116") (name "/w93") (class "Default")
      (node (ref "FD12") (pin "14") (pinfunction "OT5_14") (pintype "passive"))
      (node (ref "T") (pin "16") (pinfunction "P16_16") (pintype "passive"))
    )
    (net (code "117") (name "/w94") (class "Default")
      (node (ref "FD12") (pin "13") (pinfunction "OT6_13") (pintype "passive"))
      (node (ref "T") (pin "36") (pinfunction "P36_36") (pintype "passive"))
    )
    (net (code "118") (name "/w95") (class "Default")
      (node (ref "FD12") (pin "12") (pinfunction "OT7_12") (pintype "passive"))
      (node (ref "M") (pin "36") (pinfunction "P36_36") (pintype "passive"))
    )
    (net (code "119") (name "/w96") (class "Default")
      (node (ref "B") (pin "36") (pinfunction "P36_36") (pintype "passive"))
      (node (ref "FD12") (pin "11") (pinfunction "OT8_11") (pintype "passive"))
    )
    (net (code "120") (name "/w97") (class "Default")
      (node (ref "B") (pin "17") (pinfunction "P17_17") (pintype "passive"))
      (node (ref "FD13") (pin "18") (pinfunction "OT1_18") (pintype "passive"))
    )
    (net (code "121") (name "/w98") (class "Default")
      (node (ref "FD13") (pin "17") (pinfunction "OT2_17") (pintype "passive"))
      (node (ref "M") (pin "17") (pinfunction "P17_17") (pintype "passive"))
    )
    (net (code "122") (name "/w99") (class "Default")
      (node (ref "FD13") (pin "16") (pinfunction "OT3_16") (pintype "passive"))
      (node (ref "T") (pin "17") (pinfunction "P17_17") (pintype "passive"))
    )
    (net (code "123") (name "/w100") (class "Default")
      (node (ref "FD13") (pin "15") (pinfunction "OT4_15") (pintype "passive"))
      (node (ref "T") (pin "37") (pinfunction "P37_37") (pintype "passive"))
    )
    (net (code "124") (name "/w101") (class "Default")
      (node (ref "FD13") (pin "14") (pinfunction "OT5_14") (pintype "passive"))
      (node (ref "M") (pin "37") (pinfunction "P37_37") (pintype "passive"))
    )
    (net (code "125") (name "/w102") (class "Default")
      (node (ref "B") (pin "37") (pinfunction "P37_37") (pintype "passive"))
      (node (ref "FD13") (pin "13") (pinfunction "OT6_13") (pintype "passive"))
    )
    (net (code "126") (name "/w103") (class "Default")
      (node (ref "B") (pin "18") (pinfunction "P18_18") (pintype "passive"))
      (node (ref "FD13") (pin "12") (pinfunction "OT7_12") (pintype "passive"))
    )
    (net (code "127") (name "/w104") (class "Default")
      (node (ref "FD13") (pin "11") (pinfunction "OT8_11") (pintype "passive"))
      (node (ref "M") (pin "18") (pinfunction "P18_18") (pintype "passive"))
    )
    (net (code "128") (name "/w105") (class "Default")
      (node (ref "FD14") (pin "18") (pinfunction "OT1_18") (pintype "passive"))
      (node (ref "T") (pin "18") (pinfunction "P18_18") (pintype "passive"))
    )
    (net (code "129") (name "/w106") (class "Default")
      (node (ref "FD14") (pin "17") (pinfunction "OT2_17") (pintype "passive"))
      (node (ref "T") (pin "38") (pinfunction "P38_38") (pintype "passive"))
    )
    (net (code "130") (name "/w107") (class "Default")
      (node (ref "FD14") (pin "16") (pinfunction "OT3_16") (pintype "passive"))
      (node (ref "M") (pin "38") (pinfunction "P38_38") (pintype "passive"))
    )
    (net (code "131") (name "/w108") (class "Default")
      (node (ref "B") (pin "38") (pinfunction "P38_38") (pintype "passive"))
      (node (ref "FD14") (pin "15") (pinfunction "OT4_15") (pintype "passive"))
    )
    (net (code "132") (name "/w109") (class "Default")
      (node (ref "B") (pin "19") (pinfunction "P19_19") (pintype "passive"))
      (node (ref "FD14") (pin "14") (pinfunction "OT5_14") (pintype "passive"))
    )
    (net (code "133") (name "/w110") (class "Default")
      (node (ref "FD14") (pin "13") (pinfunction "OT6_13") (pintype "passive"))
      (node (ref "M") (pin "19") (pinfunction "P19_19") (pintype "passive"))
    )
    (net (code "134") (name "/w111") (class "Default")
      (node (ref "FD14") (pin "12") (pinfunction "OT7_12") (pintype "passive"))
      (node (ref "T") (pin "19") (pinfunction "P19_19") (pintype "passive"))
    )
    (net (code "135") (name "/w112") (class "Default")
      (node (ref "FD14") (pin "11") (pinfunction "OT8_11") (pintype "passive"))
      (node (ref "T") (pin "39") (pinfunction "P39_39") (pintype "passive"))
    )
    (net (code "136") (name "/w113") (class "Default")
      (node (ref "FD15") (pin "18") (pinfunction "OT1_18") (pintype "passive"))
      (node (ref "M") (pin "39") (pinfunction "P39_39") (pintype "passive"))
    )
    (net (code "137") (name "/w114") (class "Default")
      (node (ref "B") (pin "39") (pinfunction "P39_39") (pintype "passive"))
      (node (ref "FD15") (pin "17") (pinfunction "OT2_17") (pintype "passive"))
    )
    (net (code "138") (name "/w115") (class "Default")
      (node (ref "B") (pin "20") (pinfunction "P20_20") (pintype "passive"))
      (node (ref "FD15") (pin "16") (pinfunction "OT3_16") (pintype "passive"))
    )
    (net (code "139") (name "/w116") (class "Default")
      (node (ref "FD15") (pin "15") (pinfunction "OT4_15") (pintype "passive"))
      (node (ref "M") (pin "20") (pinfunction "P20_20") (pintype "passive"))
    )
    (net (code "140") (name "/w117") (class "Default")
      (node (ref "FD15") (pin "14") (pinfunction "OT5_14") (pintype "passive"))
      (node (ref "T") (pin "20") (pinfunction "P20_20") (pintype "passive"))
    )
    (net (code "141") (name "/w118") (class "Default")
      (node (ref "FD15") (pin "13") (pinfunction "OT6_13") (pintype "passive"))
      (node (ref "T") (pin "40") (pinfunction "P40_40") (pintype "passive"))
    )
    (net (code "142") (name "/w119") (class "Default")
      (node (ref "FD15") (pin "12") (pinfunction "OT7_12") (pintype "passive"))
      (node (ref "M") (pin "40") (pinfunction "P40_40") (pintype "passive"))
    )
    (net (code "143") (name "/w120") (class "Default")
      (node (ref "B") (pin "40") (pinfunction "P40_40") (pintype "passive"))
      (node (ref "FD15") (pin "11") (pinfunction "OT8_11") (pintype "passive"))
    )
    (net (code "144") (name "/xq1") (class "Default")
      (node (ref "573_1") (pin "19") (pinfunction "Q1_19") (pintype "tri_state"))
      (node (ref "FD1") (pin "1") (pinfunction "IN1_1") (pintype "passive"))
    )
    (net (code "145") (name "/xq2") (class "Default")
      (node (ref "573_1") (pin "18") (pinfunction "Q2_18") (pintype "tri_state"))
      (node (ref "FD1") (pin "2") (pinfunction "IN2_2") (pintype "passive"))
    )
    (net (code "146") (name "/xq3") (class "Default")
      (node (ref "573_1") (pin "17") (pinfunction "Q3_17") (pintype "tri_state"))
      (node (ref "FD1") (pin "3") (pinfunction "IN3_3") (pintype "passive"))
    )
    (net (code "147") (name "/xq4") (class "Default")
      (node (ref "573_1") (pin "16") (pinfunction "Q4_16") (pintype "tri_state"))
      (node (ref "FD1") (pin "4") (pinfunction "IN4_4") (pintype "passive"))
    )
    (net (code "148") (name "/xq5") (class "Default")
      (node (ref "573_1") (pin "15") (pinfunction "Q5_15") (pintype "tri_state"))
      (node (ref "FD1") (pin "5") (pinfunction "IN5_5") (pintype "passive"))
    )
    (net (code "149") (name "/xq6") (class "Default")
      (node (ref "573_1") (pin "14") (pinfunction "Q6_14") (pintype "tri_state"))
      (node (ref "FD1") (pin "6") (pinfunction "IN6_6") (pintype "passive"))
    )
    (net (code "150") (name "/xq7") (class "Default")
      (node (ref "573_1") (pin "13") (pinfunction "Q7_13") (pintype "tri_state"))
      (node (ref "FD1") (pin "7") (pinfunction "IN7_7") (pintype "passive"))
    )
    (net (code "151") (name "/xq8") (class "Default")
      (node (ref "573_1") (pin "12") (pinfunction "Q8_12") (pintype "tri_state"))
      (node (ref "FD1") (pin "8") (pinfunction "IN8_8") (pintype "passive"))
    )
    (net (code "152") (name "/xq9") (class "Default")
      (node (ref "573_2") (pin "19") (pinfunction "Q1_19") (pintype "tri_state"))
      (node (ref "FD2") (pin "1") (pinfunction "IN1_1") (pintype "passive"))
    )
    (net (code "153") (name "/xq10") (class "Default")
      (node (ref "573_2") (pin "18") (pinfunction "Q2_18") (pintype "tri_state"))
      (node (ref "FD2") (pin "2") (pinfunction "IN2_2") (pintype "passive"))
    )
    (net (code "154") (name "/xq11") (class "Default")
      (node (ref "573_2") (pin "17") (pinfunction "Q3_17") (pintype "tri_state"))
      (node (ref "FD2") (pin "3") (pinfunction "IN3_3") (pintype "passive"))
    )
    (net (code "155") (name "/xq12") (class "Default")
      (node (ref "573_2") (pin "16") (pinfunction "Q4_16") (pintype "tri_state"))
      (node (ref "FD2") (pin "4") (pinfunction "IN4_4") (pintype "passive"))
    )
    (net (code "156") (name "/xq13") (class "Default")
      (node (ref "573_2") (pin "15") (pinfunction "Q5_15") (pintype "tri_state"))
      (node (ref "FD2") (pin "5") (pinfunction "IN5_5") (pintype "passive"))
    )
    (net (code "157") (name "/xq14") (class "Default")
      (node (ref "573_2") (pin "14") (pinfunction "Q6_14") (pintype "tri_state"))
      (node (ref "FD2") (pin "6") (pinfunction "IN6_6") (pintype "passive"))
    )
    (net (code "158") (name "/xq15") (class "Default")
      (node (ref "573_2") (pin "13") (pinfunction "Q7_13") (pintype "tri_state"))
      (node (ref "FD2") (pin "7") (pinfunction "IN7_7") (pintype "passive"))
    )
    (net (code "159") (name "/xq16") (class "Default")
      (node (ref "573_2") (pin "12") (pinfunction "Q8_12") (pintype "tri_state"))
      (node (ref "FD2") (pin "8") (pinfunction "IN8_8") (pintype "passive"))
    )
    (net (code "160") (name "/xq17") (class "Default")
      (node (ref "573_3") (pin "19") (pinfunction "Q1_19") (pintype "tri_state"))
      (node (ref "FD3") (pin "1") (pinfunction "IN1_1") (pintype "passive"))
    )
    (net (code "161") (name "/xq18") (class "Default")
      (node (ref "573_3") (pin "18") (pinfunction "Q2_18") (pintype "tri_state"))
      (node (ref "FD3") (pin "2") (pinfunction "IN2_2") (pintype "passive"))
    )
    (net (code "162") (name "/xq19") (class "Default")
      (node (ref "573_3") (pin "17") (pinfunction "Q3_17") (pintype "tri_state"))
      (node (ref "FD3") (pin "3") (pinfunction "IN3_3") (pintype "passive"))
    )
    (net (code "163") (name "/xq20") (class "Default")
      (node (ref "573_3") (pin "16") (pinfunction "Q4_16") (pintype "tri_state"))
      (node (ref "FD3") (pin "4") (pinfunction "IN4_4") (pintype "passive"))
    )
    (net (code "164") (name "/xq21") (class "Default")
      (node (ref "573_3") (pin "15") (pinfunction "Q5_15") (pintype "tri_state"))
      (node (ref "FD3") (pin "5") (pinfunction "IN5_5") (pintype "passive"))
    )
    (net (code "165") (name "/xq22") (class "Default")
      (node (ref "573_3") (pin "14") (pinfunction "Q6_14") (pintype "tri_state"))
      (node (ref "FD3") (pin "6") (pinfunction "IN6_6") (pintype "passive"))
    )
    (net (code "166") (name "/xq23") (class "Default")
      (node (ref "573_3") (pin "13") (pinfunction "Q7_13") (pintype "tri_state"))
      (node (ref "FD3") (pin "7") (pinfunction "IN7_7") (pintype "passive"))
    )
    (net (code "167") (name "/xq24") (class "Default")
      (node (ref "573_3") (pin "12") (pinfunction "Q8_12") (pintype "tri_state"))
      (node (ref "FD3") (pin "8") (pinfunction "IN8_8") (pintype "passive"))
    )
    (net (code "168") (name "/xq25") (class "Default")
      (node (ref "573_4") (pin "19") (pinfunction "Q1_19") (pintype "tri_state"))
      (node (ref "FD4") (pin "1") (pinfunction "IN1_1") (pintype "passive"))
    )
    (net (code "169") (name "/xq26") (class "Default")
      (node (ref "573_4") (pin "18") (pinfunction "Q2_18") (pintype "tri_state"))
      (node (ref "FD4") (pin "2") (pinfunction "IN2_2") (pintype "passive"))
    )
    (net (code "170") (name "/xq27") (class "Default")
      (node (ref "573_4") (pin "17") (pinfunction "Q3_17") (pintype "tri_state"))
      (node (ref "FD4") (pin "3") (pinfunction "IN3_3") (pintype "passive"))
    )
    (net (code "171") (name "/xq28") (class "Default")
      (node (ref "573_4") (pin "16") (pinfunction "Q4_16") (pintype "tri_state"))
      (node (ref "FD4") (pin "4") (pinfunction "IN4_4") (pintype "passive"))
    )
    (net (code "172") (name "/xq29") (class "Default")
      (node (ref "573_4") (pin "15") (pinfunction "Q5_15") (pintype "tri_state"))
      (node (ref "FD4") (pin "5") (pinfunction "IN5_5") (pintype "passive"))
    )
    (net (code "173") (name "/xq30") (class "Default")
      (node (ref "573_4") (pin "14") (pinfunction "Q6_14") (pintype "tri_state"))
      (node (ref "FD4") (pin "6") (pinfunction "IN6_6") (pintype "passive"))
    )
    (net (code "174") (name "/xq31") (class "Default")
      (node (ref "573_4") (pin "13") (pinfunction "Q7_13") (pintype "tri_state"))
      (node (ref "FD4") (pin "7") (pinfunction "IN7_7") (pintype "passive"))
    )
    (net (code "175") (name "/xq32") (class "Default")
      (node (ref "573_4") (pin "12") (pinfunction "Q8_12") (pintype "tri_state"))
      (node (ref "FD4") (pin "8") (pinfunction "IN8_8") (pintype "passive"))
    )
    (net (code "176") (name "/xq33") (class "Default")
      (node (ref "573_5") (pin "19") (pinfunction "Q1_19") (pintype "tri_state"))
      (node (ref "FD5") (pin "1") (pinfunction "IN1_1") (pintype "passive"))
    )
    (net (code "177") (name "/xq34") (class "Default")
      (node (ref "573_5") (pin "18") (pinfunction "Q2_18") (pintype "tri_state"))
      (node (ref "FD5") (pin "2") (pinfunction "IN2_2") (pintype "passive"))
    )
    (net (code "178") (name "/xq35") (class "Default")
      (node (ref "573_5") (pin "17") (pinfunction "Q3_17") (pintype "tri_state"))
      (node (ref "FD5") (pin "3") (pinfunction "IN3_3") (pintype "passive"))
    )
    (net (code "179") (name "/xq36") (class "Default")
      (node (ref "573_5") (pin "16") (pinfunction "Q4_16") (pintype "tri_state"))
      (node (ref "FD5") (pin "4") (pinfunction "IN4_4") (pintype "passive"))
    )
    (net (code "180") (name "/xq37") (class "Default")
      (node (ref "573_5") (pin "15") (pinfunction "Q5_15") (pintype "tri_state"))
      (node (ref "FD5") (pin "5") (pinfunction "IN5_5") (pintype "passive"))
    )
    (net (code "181") (name "/xq38") (class "Default")
      (node (ref "573_5") (pin "14") (pinfunction "Q6_14") (pintype "tri_state"))
      (node (ref "FD5") (pin "6") (pinfunction "IN6_6") (pintype "passive"))
    )
    (net (code "182") (name "/xq39") (class "Default")
      (node (ref "573_5") (pin "13") (pinfunction "Q7_13") (pintype "tri_state"))
      (node (ref "FD5") (pin "7") (pinfunction "IN7_7") (pintype "passive"))
    )
    (net (code "183") (name "/xq40") (class "Default")
      (node (ref "573_5") (pin "12") (pinfunction "Q8_12") (pintype "tri_state"))
      (node (ref "FD5") (pin "8") (pinfunction "IN8_8") (pintype "passive"))
    )
    (net (code "184") (name "/xq41") (class "Default")
      (node (ref "573_7") (pin "19") (pinfunction "Q1_19") (pintype "tri_state"))
      (node (ref "FD6") (pin "1") (pinfunction "IN1_1") (pintype "passive"))
    )
    (net (code "185") (name "/xq42") (class "Default")
      (node (ref "573_7") (pin "18") (pinfunction "Q2_18") (pintype "tri_state"))
      (node (ref "FD6") (pin "2") (pinfunction "IN2_2") (pintype "passive"))
    )
    (net (code "186") (name "/xq43") (class "Default")
      (node (ref "573_7") (pin "17") (pinfunction "Q3_17") (pintype "tri_state"))
      (node (ref "FD6") (pin "3") (pinfunction "IN3_3") (pintype "passive"))
    )
    (net (code "187") (name "/xq44") (class "Default")
      (node (ref "573_7") (pin "16") (pinfunction "Q4_16") (pintype "tri_state"))
      (node (ref "FD6") (pin "4") (pinfunction "IN4_4") (pintype "passive"))
    )
    (net (code "188") (name "/xq45") (class "Default")
      (node (ref "573_7") (pin "15") (pinfunction "Q5_15") (pintype "tri_state"))
      (node (ref "FD6") (pin "5") (pinfunction "IN5_5") (pintype "passive"))
    )
    (net (code "189") (name "/xq46") (class "Default")
      (node (ref "573_7") (pin "14") (pinfunction "Q6_14") (pintype "tri_state"))
      (node (ref "FD6") (pin "6") (pinfunction "IN6_6") (pintype "passive"))
    )
    (net (code "190") (name "/xq47") (class "Default")
      (node (ref "573_7") (pin "13") (pinfunction "Q7_13") (pintype "tri_state"))
      (node (ref "FD6") (pin "7") (pinfunction "IN7_7") (pintype "passive"))
    )
    (net (code "191") (name "/xq48") (class "Default")
      (node (ref "573_7") (pin "12") (pinfunction "Q8_12") (pintype "tri_state"))
      (node (ref "FD6") (pin "8") (pinfunction "IN8_8") (pintype "passive"))
    )
    (net (code "192") (name "/xq49") (class "Default")
      (node (ref "573_8") (pin "19") (pinfunction "Q1_19") (pintype "tri_state"))
      (node (ref "FD7") (pin "1") (pinfunction "IN1_1") (pintype "passive"))
    )
    (net (code "193") (name "/xq50") (class "Default")
      (node (ref "573_8") (pin "18") (pinfunction "Q2_18") (pintype "tri_state"))
      (node (ref "FD7") (pin "2") (pinfunction "IN2_2") (pintype "passive"))
    )
    (net (code "194") (name "/xq51") (class "Default")
      (node (ref "573_8") (pin "17") (pinfunction "Q3_17") (pintype "tri_state"))
      (node (ref "FD7") (pin "3") (pinfunction "IN3_3") (pintype "passive"))
    )
    (net (code "195") (name "/xq52") (class "Default")
      (node (ref "573_8") (pin "16") (pinfunction "Q4_16") (pintype "tri_state"))
      (node (ref "FD7") (pin "4") (pinfunction "IN4_4") (pintype "passive"))
    )
    (net (code "196") (name "/xq53") (class "Default")
      (node (ref "573_8") (pin "15") (pinfunction "Q5_15") (pintype "tri_state"))
      (node (ref "FD7") (pin "5") (pinfunction "IN5_5") (pintype "passive"))
    )
    (net (code "197") (name "/xq54") (class "Default")
      (node (ref "573_8") (pin "14") (pinfunction "Q6_14") (pintype "tri_state"))
      (node (ref "FD7") (pin "6") (pinfunction "IN6_6") (pintype "passive"))
    )
    (net (code "198") (name "/xq55") (class "Default")
      (node (ref "573_8") (pin "13") (pinfunction "Q7_13") (pintype "tri_state"))
      (node (ref "FD7") (pin "7") (pinfunction "IN7_7") (pintype "passive"))
    )
    (net (code "199") (name "/xq56") (class "Default")
      (node (ref "573_8") (pin "12") (pinfunction "Q8_12") (pintype "tri_state"))
      (node (ref "FD7") (pin "8") (pinfunction "IN8_8") (pintype "passive"))
    )
    (net (code "200") (name "/xq57") (class "Default")
      (node (ref "573_9") (pin "19") (pinfunction "Q1_19") (pintype "tri_state"))
      (node (ref "FD8") (pin "1") (pinfunction "IN1_1") (pintype "passive"))
    )
    (net (code "201") (name "/xq58") (class "Default")
      (node (ref "573_9") (pin "18") (pinfunction "Q2_18") (pintype "tri_state"))
      (node (ref "FD8") (pin "2") (pinfunction "IN2_2") (pintype "passive"))
    )
    (net (code "202") (name "/xq59") (class "Default")
      (node (ref "573_9") (pin "17") (pinfunction "Q3_17") (pintype "tri_state"))
      (node (ref "FD8") (pin "3") (pinfunction "IN3_3") (pintype "passive"))
    )
    (net (code "203") (name "/xq60") (class "Default")
      (node (ref "573_9") (pin "16") (pinfunction "Q4_16") (pintype "tri_state"))
      (node (ref "FD8") (pin "4") (pinfunction "IN4_4") (pintype "passive"))
    )
    (net (code "204") (name "/xq61") (class "Default")
      (node (ref "573_9") (pin "15") (pinfunction "Q5_15") (pintype "tri_state"))
      (node (ref "FD8") (pin "5") (pinfunction "IN5_5") (pintype "passive"))
    )
    (net (code "205") (name "/xq62") (class "Default")
      (node (ref "573_9") (pin "14") (pinfunction "Q6_14") (pintype "tri_state"))
      (node (ref "FD8") (pin "6") (pinfunction "IN6_6") (pintype "passive"))
    )
    (net (code "206") (name "/xq63") (class "Default")
      (node (ref "573_9") (pin "13") (pinfunction "Q7_13") (pintype "tri_state"))
      (node (ref "FD8") (pin "7") (pinfunction "IN7_7") (pintype "passive"))
    )
    (net (code "207") (name "/xq64") (class "Default")
      (node (ref "573_9") (pin "12") (pinfunction "Q8_12") (pintype "tri_state"))
      (node (ref "FD8") (pin "8") (pinfunction "IN8_8") (pintype "passive"))
    )
    (net (code "208") (name "/xq65") (class "Default")
      (node (ref "573_10") (pin "19") (pinfunction "Q1_19") (pintype "tri_state"))
      (node (ref "FD9") (pin "1") (pinfunction "IN1_1") (pintype "passive"))
    )
    (net (code "209") (name "/xq66") (class "Default")
      (node (ref "573_10") (pin "18") (pinfunction "Q2_18") (pintype "tri_state"))
      (node (ref "FD9") (pin "2") (pinfunction "IN2_2") (pintype "passive"))
    )
    (net (code "210") (name "/xq67") (class "Default")
      (node (ref "573_10") (pin "17") (pinfunction "Q3_17") (pintype "tri_state"))
      (node (ref "FD9") (pin "3") (pinfunction "IN3_3") (pintype "passive"))
    )
    (net (code "211") (name "/xq68") (class "Default")
      (node (ref "573_10") (pin "16") (pinfunction "Q4_16") (pintype "tri_state"))
      (node (ref "FD9") (pin "4") (pinfunction "IN4_4") (pintype "passive"))
    )
    (net (code "212") (name "/xq69") (class "Default")
      (node (ref "573_10") (pin "15") (pinfunction "Q5_15") (pintype "tri_state"))
      (node (ref "FD9") (pin "5") (pinfunction "IN5_5") (pintype "passive"))
    )
    (net (code "213") (name "/xq70") (class "Default")
      (node (ref "573_10") (pin "14") (pinfunction "Q6_14") (pintype "tri_state"))
      (node (ref "FD9") (pin "6") (pinfunction "IN6_6") (pintype "passive"))
    )
    (net (code "214") (name "/xq71") (class "Default")
      (node (ref "573_10") (pin "13") (pinfunction "Q7_13") (pintype "tri_state"))
      (node (ref "FD9") (pin "7") (pinfunction "IN7_7") (pintype "passive"))
    )
    (net (code "215") (name "/xq72") (class "Default")
      (node (ref "573_10") (pin "12") (pinfunction "Q8_12") (pintype "tri_state"))
      (node (ref "FD9") (pin "8") (pinfunction "IN8_8") (pintype "passive"))
    )
    (net (code "216") (name "/xq73") (class "Default")
      (node (ref "573_11") (pin "19") (pinfunction "Q1_19") (pintype "tri_state"))
      (node (ref "FD10") (pin "1") (pinfunction "IN1_1") (pintype "passive"))
    )
    (net (code "217") (name "/xq74") (class "Default")
      (node (ref "573_11") (pin "18") (pinfunction "Q2_18") (pintype "tri_state"))
      (node (ref "FD10") (pin "2") (pinfunction "IN2_2") (pintype "passive"))
    )
    (net (code "218") (name "/xq75") (class "Default")
      (node (ref "573_11") (pin "17") (pinfunction "Q3_17") (pintype "tri_state"))
      (node (ref "FD10") (pin "3") (pinfunction "IN3_3") (pintype "passive"))
    )
    (net (code "219") (name "/xq76") (class "Default")
      (node (ref "573_11") (pin "16") (pinfunction "Q4_16") (pintype "tri_state"))
      (node (ref "FD10") (pin "4") (pinfunction "IN4_4") (pintype "passive"))
    )
    (net (code "220") (name "/xq77") (class "Default")
      (node (ref "573_11") (pin "15") (pinfunction "Q5_15") (pintype "tri_state"))
      (node (ref "FD10") (pin "5") (pinfunction "IN5_5") (pintype "passive"))
    )
    (net (code "221") (name "/xq78") (class "Default")
      (node (ref "573_11") (pin "14") (pinfunction "Q6_14") (pintype "tri_state"))
      (node (ref "FD10") (pin "6") (pinfunction "IN6_6") (pintype "passive"))
    )
    (net (code "222") (name "/xq79") (class "Default")
      (node (ref "573_11") (pin "13") (pinfunction "Q7_13") (pintype "tri_state"))
      (node (ref "FD10") (pin "7") (pinfunction "IN7_7") (pintype "passive"))
    )
    (net (code "223") (name "/xq80") (class "Default")
      (node (ref "573_11") (pin "12") (pinfunction "Q8_12") (pintype "tri_state"))
      (node (ref "FD10") (pin "8") (pinfunction "IN8_8") (pintype "passive"))
    )
    (net (code "224") (name "/xq81") (class "Default")
      (node (ref "573_12") (pin "19") (pinfunction "Q1_19") (pintype "tri_state"))
      (node (ref "FD11") (pin "1") (pinfunction "IN1_1") (pintype "passive"))
    )
    (net (code "225") (name "/xq82") (class "Default")
      (node (ref "573_12") (pin "18") (pinfunction "Q2_18") (pintype "tri_state"))
      (node (ref "FD11") (pin "2") (pinfunction "IN2_2") (pintype "passive"))
    )
    (net (code "226") (name "/xq83") (class "Default")
      (node (ref "573_12") (pin "17") (pinfunction "Q3_17") (pintype "tri_state"))
      (node (ref "FD11") (pin "3") (pinfunction "IN3_3") (pintype "passive"))
    )
    (net (code "227") (name "/xq84") (class "Default")
      (node (ref "573_12") (pin "16") (pinfunction "Q4_16") (pintype "tri_state"))
      (node (ref "FD11") (pin "4") (pinfunction "IN4_4") (pintype "passive"))
    )
    (net (code "228") (name "/xq85") (class "Default")
      (node (ref "573_12") (pin "15") (pinfunction "Q5_15") (pintype "tri_state"))
      (node (ref "FD11") (pin "5") (pinfunction "IN5_5") (pintype "passive"))
    )
    (net (code "229") (name "/xq86") (class "Default")
      (node (ref "573_12") (pin "14") (pinfunction "Q6_14") (pintype "tri_state"))
      (node (ref "FD11") (pin "6") (pinfunction "IN6_6") (pintype "passive"))
    )
    (net (code "230") (name "/xq87") (class "Default")
      (node (ref "573_12") (pin "13") (pinfunction "Q7_13") (pintype "tri_state"))
      (node (ref "FD11") (pin "7") (pinfunction "IN7_7") (pintype "passive"))
    )
    (net (code "231") (name "/xq88") (class "Default")
      (node (ref "573_12") (pin "12") (pinfunction "Q8_12") (pintype "tri_state"))
      (node (ref "FD11") (pin "8") (pinfunction "IN8_8") (pintype "passive"))
    )
    (net (code "232") (name "/xq89") (class "Default")
      (node (ref "573_13") (pin "19") (pinfunction "Q1_19") (pintype "tri_state"))
      (node (ref "FD12") (pin "1") (pinfunction "IN1_1") (pintype "passive"))
    )
    (net (code "233") (name "/xq90") (class "Default")
      (node (ref "573_13") (pin "18") (pinfunction "Q2_18") (pintype "tri_state"))
      (node (ref "FD12") (pin "2") (pinfunction "IN2_2") (pintype "passive"))
    )
    (net (code "234") (name "/xq91") (class "Default")
      (node (ref "573_13") (pin "17") (pinfunction "Q3_17") (pintype "tri_state"))
      (node (ref "FD12") (pin "3") (pinfunction "IN3_3") (pintype "passive"))
    )
    (net (code "235") (name "/xq92") (class "Default")
      (node (ref "573_13") (pin "16") (pinfunction "Q4_16") (pintype "tri_state"))
      (node (ref "FD12") (pin "4") (pinfunction "IN4_4") (pintype "passive"))
    )
    (net (code "236") (name "/xq93") (class "Default")
      (node (ref "573_13") (pin "15") (pinfunction "Q5_15") (pintype "tri_state"))
      (node (ref "FD12") (pin "5") (pinfunction "IN5_5") (pintype "passive"))
    )
    (net (code "237") (name "/xq94") (class "Default")
      (node (ref "573_13") (pin "14") (pinfunction "Q6_14") (pintype "tri_state"))
      (node (ref "FD12") (pin "6") (pinfunction "IN6_6") (pintype "passive"))
    )
    (net (code "238") (name "/xq95") (class "Default")
      (node (ref "573_13") (pin "13") (pinfunction "Q7_13") (pintype "tri_state"))
      (node (ref "FD12") (pin "7") (pinfunction "IN7_7") (pintype "passive"))
    )
    (net (code "239") (name "/xq96") (class "Default")
      (node (ref "573_13") (pin "12") (pinfunction "Q8_12") (pintype "tri_state"))
      (node (ref "FD12") (pin "8") (pinfunction "IN8_8") (pintype "passive"))
    )
    (net (code "240") (name "/xq97") (class "Default")
      (node (ref "573_14") (pin "19") (pinfunction "Q1_19") (pintype "tri_state"))
      (node (ref "FD13") (pin "1") (pinfunction "IN1_1") (pintype "passive"))
    )
    (net (code "241") (name "/xq98") (class "Default")
      (node (ref "573_14") (pin "18") (pinfunction "Q2_18") (pintype "tri_state"))
      (node (ref "FD13") (pin "2") (pinfunction "IN2_2") (pintype "passive"))
    )
    (net (code "242") (name "/xq99") (class "Default")
      (node (ref "573_14") (pin "17") (pinfunction "Q3_17") (pintype "tri_state"))
      (node (ref "FD13") (pin "3") (pinfunction "IN3_3") (pintype "passive"))
    )
    (net (code "243") (name "/xq100") (class "Default")
      (node (ref "573_14") (pin "16") (pinfunction "Q4_16") (pintype "tri_state"))
      (node (ref "FD13") (pin "4") (pinfunction "IN4_4") (pintype "passive"))
    )
    (net (code "244") (name "/xq101") (class "Default")
      (node (ref "573_14") (pin "15") (pinfunction "Q5_15") (pintype "tri_state"))
      (node (ref "FD13") (pin "5") (pinfunction "IN5_5") (pintype "passive"))
    )
    (net (code "245") (name "/xq102") (class "Default")
      (node (ref "573_14") (pin "14") (pinfunction "Q6_14") (pintype "tri_state"))
      (node (ref "FD13") (pin "6") (pinfunction "IN6_6") (pintype "passive"))
    )
    (net (code "246") (name "/xq103") (class "Default")
      (node (ref "573_14") (pin "13") (pinfunction "Q7_13") (pintype "tri_state"))
      (node (ref "FD13") (pin "7") (pinfunction "IN7_7") (pintype "passive"))
    )
    (net (code "247") (name "/xq104") (class "Default")
      (node (ref "573_14") (pin "12") (pinfunction "Q8_12") (pintype "tri_state"))
      (node (ref "FD13") (pin "8") (pinfunction "IN8_8") (pintype "passive"))
    )
    (net (code "248") (name "/xq105") (class "Default")
      (node (ref "573_15") (pin "19") (pinfunction "Q1_19") (pintype "tri_state"))
      (node (ref "FD14") (pin "1") (pinfunction "IN1_1") (pintype "passive"))
    )
    (net (code "249") (name "/xq106") (class "Default")
      (node (ref "573_15") (pin "18") (pinfunction "Q2_18") (pintype "tri_state"))
      (node (ref "FD14") (pin "2") (pinfunction "IN2_2") (pintype "passive"))
    )
    (net (code "250") (name "/xq107") (class "Default")
      (node (ref "573_15") (pin "17") (pinfunction "Q3_17") (pintype "tri_state"))
      (node (ref "FD14") (pin "3") (pinfunction "IN3_3") (pintype "passive"))
    )
    (net (code "251") (name "/xq108") (class "Default")
      (node (ref "573_15") (pin "16") (pinfunction "Q4_16") (pintype "tri_state"))
      (node (ref "FD14") (pin "4") (pinfunction "IN4_4") (pintype "passive"))
    )
    (net (code "252") (name "/xq109") (class "Default")
      (node (ref "573_15") (pin "15") (pinfunction "Q5_15") (pintype "tri_state"))
      (node (ref "FD14") (pin "5") (pinfunction "IN5_5") (pintype "passive"))
    )
    (net (code "253") (name "/xq110") (class "Default")
      (node (ref "573_15") (pin "14") (pinfunction "Q6_14") (pintype "tri_state"))
      (node (ref "FD14") (pin "6") (pinfunction "IN6_6") (pintype "passive"))
    )
    (net (code "254") (name "/xq111") (class "Default")
      (node (ref "573_15") (pin "13") (pinfunction "Q7_13") (pintype "tri_state"))
      (node (ref "FD14") (pin "7") (pinfunction "IN7_7") (pintype "passive"))
    )
    (net (code "255") (name "/xq112") (class "Default")
      (node (ref "573_15") (pin "12") (pinfunction "Q8_12") (pintype "tri_state"))
      (node (ref "FD14") (pin "8") (pinfunction "IN8_8") (pintype "passive"))
    )
    (net (code "256") (name "/xq113") (class "Default")
      (node (ref "573_6") (pin "19") (pinfunction "Q1_19") (pintype "tri_state"))
      (node (ref "FD15") (pin "1") (pinfunction "IN1_1") (pintype "passive"))
    )
    (net (code "257") (name "/xq114") (class "Default")
      (node (ref "573_6") (pin "18") (pinfunction "Q2_18") (pintype "tri_state"))
      (node (ref "FD15") (pin "2") (pinfunction "IN2_2") (pintype "passive"))
    )
    (net (code "258") (name "/xq115") (class "Default")
      (node (ref "573_6") (pin "17") (pinfunction "Q3_17") (pintype "tri_state"))
      (node (ref "FD15") (pin "3") (pinfunction "IN3_3") (pintype "passive"))
    )
    (net (code "259") (name "/xq116") (class "Default")
      (node (ref "573_6") (pin "16") (pinfunction "Q4_16") (pintype "tri_state"))
      (node (ref "FD15") (pin "4") (pinfunction "IN4_4") (pintype "passive"))
    )
    (net (code "260") (name "/xq117") (class "Default")
      (node (ref "573_6") (pin "15") (pinfunction "Q5_15") (pintype "tri_state"))
      (node (ref "FD15") (pin "5") (pinfunction "IN5_5") (pintype "passive"))
    )
    (net (code "261") (name "/xq118") (class "Default")
      (node (ref "573_6") (pin "14") (pinfunction "Q6_14") (pintype "tri_state"))
      (node (ref "FD15") (pin "6") (pinfunction "IN6_6") (pintype "passive"))
    )
    (net (code "262") (name "/xq119") (class "Default")
      (node (ref "573_6") (pin "13") (pinfunction "Q7_13") (pintype "tri_state"))
      (node (ref "FD15") (pin "7") (pinfunction "IN7_7") (pintype "passive"))
    )
    (net (code "263") (name "/xq120") (class "Default")
      (node (ref "573_6") (pin "12") (pinfunction "Q8_12") (pintype "tri_state"))
      (node (ref "FD15") (pin "8") (pinfunction "IN8_8") (pintype "passive"))
    )
    (net (code "294") (name "GND") (class "Default")
      (node (ref "573_1") (pin "1") (pinfunction "~{OE}_1") (pintype "input"))
      (node (ref "573_1") (pin "10") (pinfunction "GND_10") (pintype "power_in"))
      (node (ref "573_10") (pin "1") (pinfunction "~{OE}_1") (pintype "input"))
      (node (ref "573_10") (pin "10") (pinfunction "GND_10") (pintype "power_in"))
      (node (ref "573_11") (pin "1") (pinfunction "~{OE}_1") (pintype "input"))
      (node (ref "573_11") (pin "10") (pinfunction "GND_10") (pintype "power_in"))
      (node (ref "573_12") (pin "1") (pinfunction "~{OE}_1") (pintype "input"))
      (node (ref "573_12") (pin "10") (pinfunction "GND_10") (pintype "power_in"))
      (node (ref "573_13") (pin "1") (pinfunction "~{OE}_1") (pintype "input"))
      (node (ref "573_13") (pin "10") (pinfunction "GND_10") (pintype "power_in"))
      (node (ref "573_14") (pin "1") (pinfunction "~{OE}_1") (pintype "input"))
      (node (ref "573_14") (pin "10") (pinfunction "GND_10") (pintype "power_in"))
      (node (ref "573_15") (pin "1") (pinfunction "~{OE}_1") (pintype "input"))
      (node (ref "573_15") (pin "10") (pinfunction "GND_10") (pintype "power_in"))
      (node (ref "573_2") (pin "1") (pinfunction "~{OE}_1") (pintype "input"))
      (node (ref "573_2") (pin "10") (pinfunction "GND_10") (pintype "power_in"))
      (node (ref "573_3") (pin "1") (pinfunction "~{OE}_1") (pintype "input"))
      (node (ref "573_3") (pin "10") (pinfunction "GND_10") (pintype "power_in"))
      (node (ref "573_4") (pin "1") (pinfunction "~{OE}_1") (pintype "input"))
      (node (ref "573_4") (pin "10") (pinfunction "GND_10") (pintype "power_in"))
      (node (ref "573_5") (pin "1") (pinfunction "~{OE}_1") (pintype "input"))
      (node (ref "573_5") (pin "10") (pinfunction "GND_10") (pintype "power_in"))
      (node (ref "573_6") (pin "1") (pinfunction "~{OE}_1") (pintype "input"))
      (node (ref "573_6") (pin "10") (pinfunction "GND_10") (pintype "power_in"))
      (node (ref "573_7") (pin "1") (pinfunction "~{OE}_1") (pintype "input"))
      (node (ref "573_7") (pin "10") (pinfunction "GND_10") (pintype "power_in"))
      (node (ref "573_8") (pin "1") (pinfunction "~{OE}_1") (pintype "input"))
      (node (ref "573_8") (pin "10") (pinfunction "GND_10") (pintype "power_in"))
      (node (ref "573_9") (pin "1") (pinfunction "~{OE}_1") (pintype "input"))
      (node (ref "573_9") (pin "10") (pinfunction "GND_10") (pintype "power_in"))
      (node (ref "FD1") (pin "9") (pinfunction "GND_9") (pintype "passive"))
      (node (ref "FD10") (pin "9") (pinfunction "GND_9") (pintype "passive"))
      (node (ref "FD11") (pin "9") (pinfunction "GND_9") (pintype "passive"))
      (node (ref "FD12") (pin "9") (pinfunction "GND_9") (pintype "passive"))
      (node (ref "FD13") (pin "9") (pinfunction "GND_9") (pintype "passive"))
      (node (ref "FD14") (pin "9") (pinfunction "GND_9") (pintype "passive"))
      (node (ref "FD15") (pin "9") (pinfunction "GND_9") (pintype "passive"))
      (node (ref "FD2") (pin "9") (pinfunction "GND_9") (pintype "passive"))
      (node (ref "FD3") (pin "9") (pinfunction "GND_9") (pintype "passive"))
      (node (ref "FD4") (pin "9") (pinfunction "GND_9") (pintype "passive"))
      (node (ref "FD5") (pin "9") (pinfunction "GND_9") (pintype "passive"))
      (node (ref "FD6") (pin "9") (pinfunction "GND_9") (pintype "passive"))
      (node (ref "FD7") (pin "9") (pinfunction "GND_9") (pintype "passive"))
      (node (ref "FD8") (pin "9") (pinfunction "GND_9") (pintype "passive"))
      (node (ref "FD9") (pin "9") (pinfunction "GND_9") (pintype "passive"))
      (node (ref "Jzong") (pin "2") (pinfunction "2_2") (pintype "passive"))
    )
    (net (code "295") (name "VCC5") (class "Default")
      (node (ref "573_1") (pin "20") (pinfunction "VCC_20") (pintype "power_in"))
      (node (ref "573_10") (pin "20") (pinfunction "VCC_20") (pintype "power_in"))
      (node (ref "573_11") (pin "20") (pinfunction "VCC_20") (pintype "power_in"))
      (node (ref "573_12") (pin "20") (pinfunction "VCC_20") (pintype "power_in"))
      (node (ref "573_13") (pin "20") (pinfunction "VCC_20") (pintype "power_in"))
      (node (ref "573_14") (pin "20") (pinfunction "VCC_20") (pintype "power_in"))
      (node (ref "573_15") (pin "20") (pinfunction "VCC_20") (pintype "power_in"))
      (node (ref "573_2") (pin "20") (pinfunction "VCC_20") (pintype "power_in"))
      (node (ref "573_3") (pin "20") (pinfunction "VCC_20") (pintype "power_in"))
      (node (ref "573_4") (pin "20") (pinfunction "VCC_20") (pintype "power_in"))
      (node (ref "573_5") (pin "20") (pinfunction "VCC_20") (pintype "power_in"))
      (node (ref "573_6") (pin "20") (pinfunction "VCC_20") (pintype "power_in"))
      (node (ref "573_7") (pin "20") (pinfunction "VCC_20") (pintype "power_in"))
      (node (ref "573_8") (pin "20") (pinfunction "VCC_20") (pintype "power_in"))
      (node (ref "573_9") (pin "20") (pinfunction "VCC_20") (pintype "power_in"))
    )
    (net (code "296") (name "XQVCC2") (class "Default")
      (node (ref "DY2") (pin "1") (pinfunction "DIANYUAN_1") (pintype "passive"))
      (node (ref "DY3") (pin "1") (pinfunction "DIANYUAN_1") (pintype "passive"))
      (node (ref "DY4") (pin "1") (pinfunction "DIANYUAN_1") (pintype "passive"))
      (node (ref "FD1") (pin "10") (pinfunction "COM_10") (pintype "passive"))
      (node (ref "FD10") (pin "10") (pinfunction "COM_10") (pintype "passive"))
      (node (ref "FD11") (pin "10") (pinfunction "COM_10") (pintype "passive"))
      (node (ref "FD12") (pin "10") (pinfunction "COM_10") (pintype "passive"))
      (node (ref "FD13") (pin "10") (pinfunction "COM_10") (pintype "passive"))
      (node (ref "FD14") (pin "10") (pinfunction "COM_10") (pintype "passive"))
      (node (ref "FD15") (pin "10") (pinfunction "COM_10") (pintype "passive"))
      (node (ref "FD2") (pin "10") (pinfunction "COM_10") (pintype "passive"))
      (node (ref "FD3") (pin "10") (pinfunction "COM_10") (pintype "passive"))
      (node (ref "FD4") (pin "10") (pinfunction "COM_10") (pintype "passive"))
      (node (ref "FD5") (pin "10") (pinfunction "COM_10") (pintype "passive"))
      (node (ref "FD6") (pin "10") (pinfunction "COM_10") (pintype "passive"))
      (node (ref "FD7") (pin "10") (pinfunction "COM_10") (pintype "passive"))
      (node (ref "FD8") (pin "10") (pinfunction "COM_10") (pintype "passive"))
      (node (ref "FD9") (pin "10") (pinfunction "COM_10") (pintype "passive"))
      (node (ref "Jzong") (pin "1") (pinfunction "1_1") (pintype "passive"))
    )
  )
)
